# Voltage_Regulator_Board.net
KiCad netlist of a schematic drawn in EAGLE
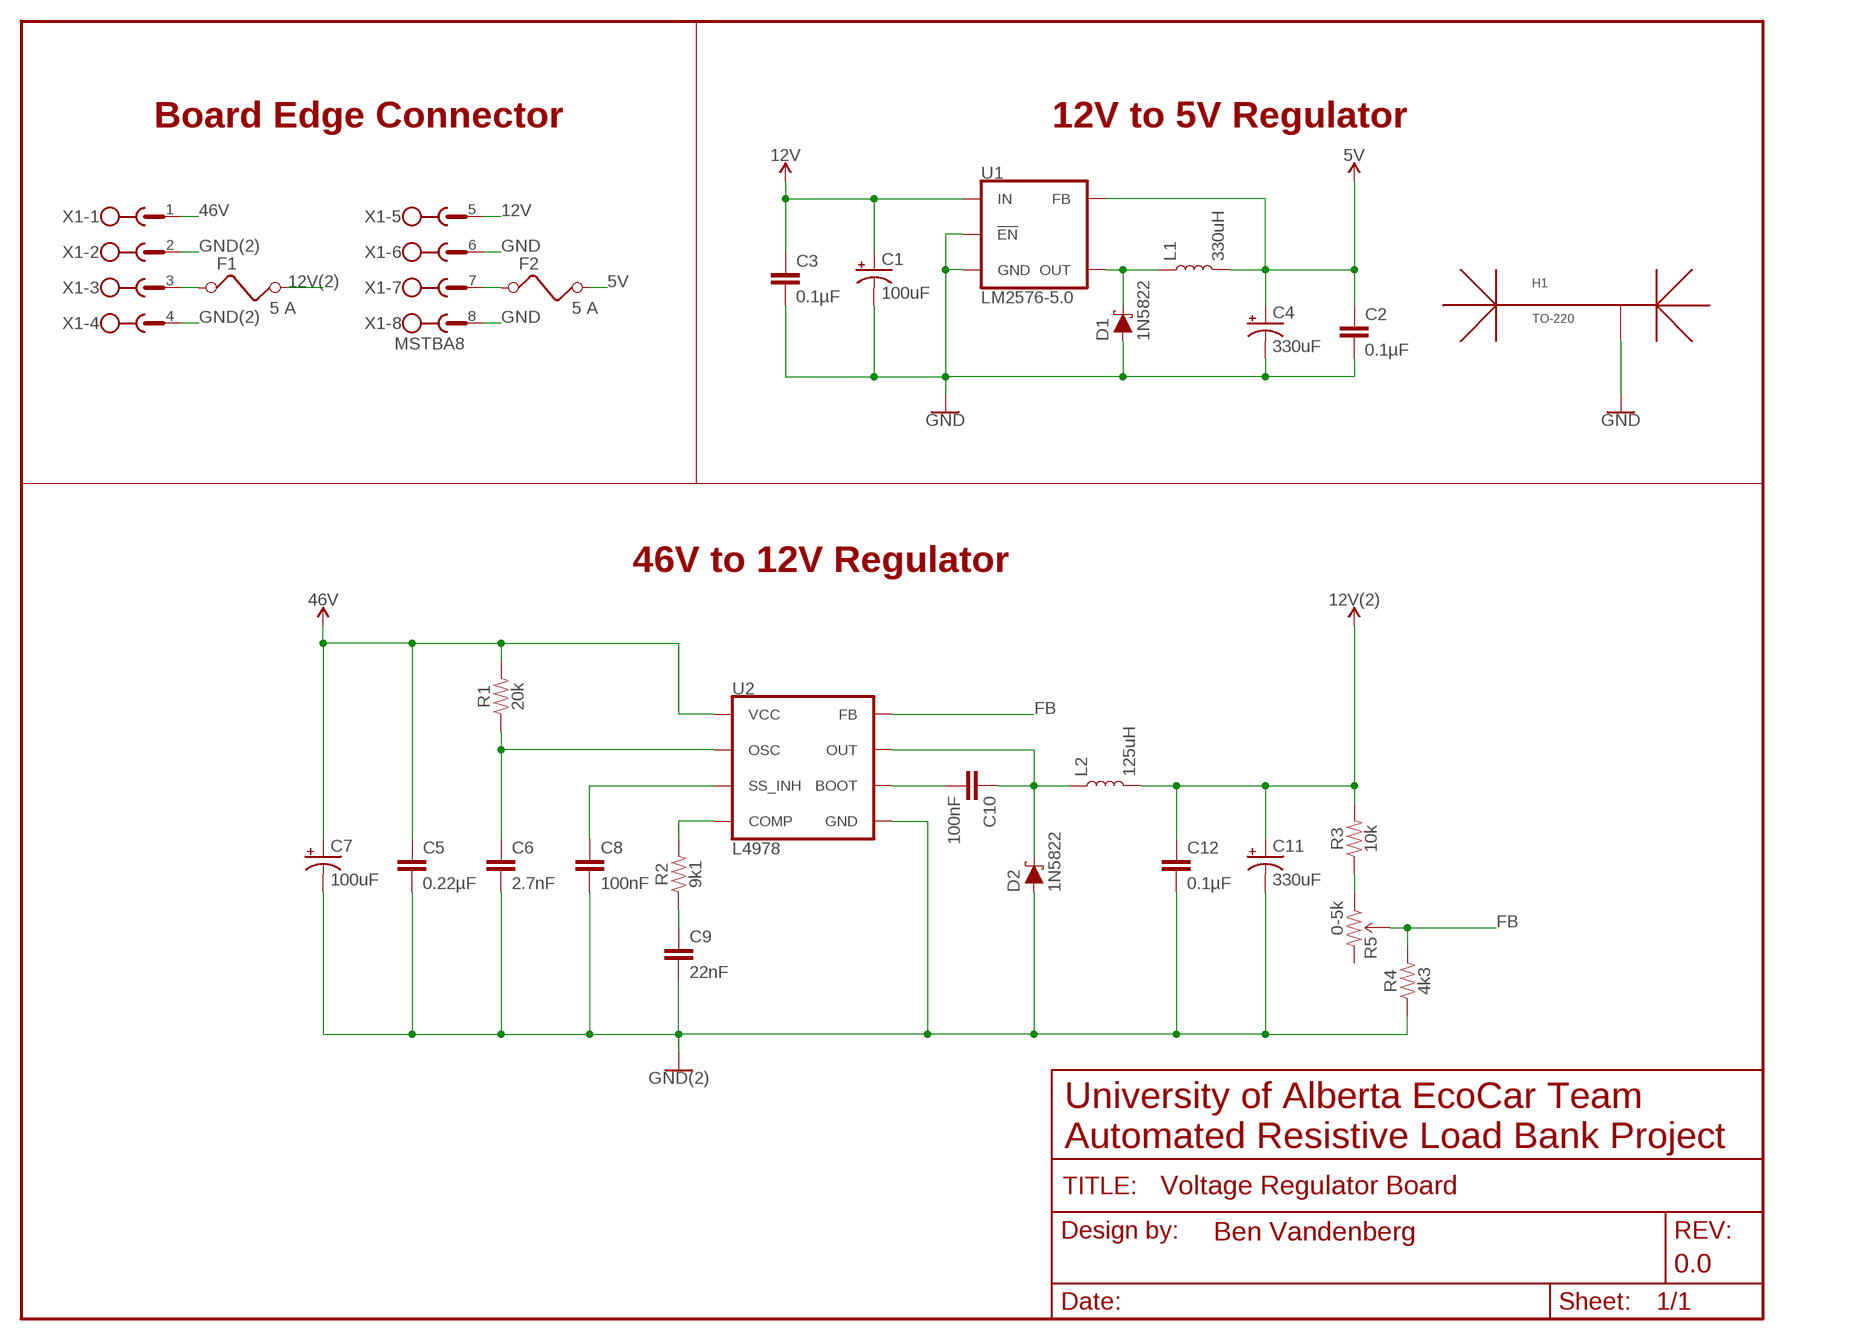
[diagram p0: schematic, sheet 1]

(export (version "E")
  (design (tool "Eeschema 10.0.6"))
  (components
    (comp (ref "C1")
      (value "100uF")
      (footprint "eagle-import:CPOL-RADIAL-3.5MM-8MM")
      (libsource (lib "eagle-import") (part "100UF_POLAR_CAP_WURTH"))
    )
    (comp (ref "C2")
      (value "0.1µF")
      (footprint "eagle-import:0805")
      (libsource (lib "eagle-import") (part "0.33UF/330NF-0805-50V-10%"))
    )
    (comp (ref "C3")
      (value "0.1µF")
      (footprint "eagle-import:0805")
      (libsource (lib "eagle-import") (part "0.33UF/330NF-0805-50V-10%"))
    )
    (comp (ref "C4")
      (value "330uF")
      (footprint "eagle-import:CPOL-RADIAL-5MM-10MM")
      (libsource (lib "eagle-import") (part "330UF_POLAR_CAP_PANASONIC"))
    )
    (comp (ref "C5")
      (value "0.22µF")
      (footprint "eagle-import:0805")
      (libsource (lib "eagle-import") (part "0.33UF/330NF-0805-50V-10%"))
    )
    (comp (ref "C6")
      (value "2.7nF")
      (footprint "eagle-import:0805")
      (libsource (lib "eagle-import") (part "0.33UF/330NF-0805-50V-10%"))
    )
    (comp (ref "C7")
      (value "100uF")
      (footprint "eagle-import:CPOL-RADIAL-3.5MM-8MM")
      (libsource (lib "eagle-import") (part "100UF_POLAR_CAP_WURTH"))
    )
    (comp (ref "C8")
      (value "100nF")
      (footprint "eagle-import:0805")
      (libsource (lib "eagle-import") (part "0.33UF/330NF-0805-50V-10%"))
    )
    (comp (ref "C9")
      (value "22nF")
      (footprint "eagle-import:0805")
      (libsource (lib "eagle-import") (part "0.33UF/330NF-0805-50V-10%"))
    )
    (comp (ref "C10")
      (value "100nF")
      (footprint "eagle-import:0805")
      (libsource (lib "eagle-import") (part "0.33UF/330NF-0805-50V-10%"))
    )
    (comp (ref "C11")
      (value "330uF")
      (footprint "eagle-import:CPOL-RADIAL-5MM-10MM")
      (libsource (lib "eagle-import") (part "330UF_POLAR_CAP_PANASONIC"))
    )
    (comp (ref "C12")
      (value "0.1µF")
      (footprint "eagle-import:0805")
      (libsource (lib "eagle-import") (part "0.33UF/330NF-0805-50V-10%"))
    )
    (comp (ref "D1")
      (value "1N5822")
      (footprint "eagle-import:DO201T15")
      (libsource (lib "eagle-import") (part "1N5822_SCHOTTKY_DIODE"))
    )
    (comp (ref "D2")
      (value "1N5822")
      (footprint "eagle-import:DO201T15")
      (libsource (lib "eagle-import") (part "1N5822_SCHOTTKY_DIODE"))
    )
    (comp (ref "F1")
      (value "5 A")
      (footprint "eagle-import:KEYSTONE_ATM_FUSEHOLDER")
      (libsource (lib "eagle-import") (part "KEYSTONE_ATM_FUSEHOLDER"))
    )
    (comp (ref "F2")
      (value "5 A")
      (footprint "eagle-import:KEYSTONE_ATM_FUSEHOLDER")
      (libsource (lib "eagle-import") (part "KEYSTONE_ATM_FUSEHOLDER"))
    )
    (comp (ref "FRAME1")
      (value "FRAME-LETTERNO_PACKAGE")
      (footprint "eagle-import:DUMMY")
      (fields
        (field (name "DESIGNER") "Nobody")
        (field (name "DESIGNER_1") "Ben Vandenberg")
        (field (name "REV") "0.0")
      )
      (libsource (lib "eagle-import") (part "FRAME-LETTERNO_PACKAGE"))
    )
    (comp (ref "H1")
      (value "TO-220")
      (footprint "eagle-import:HSE-B250-04H_HEATSINK")
      (libsource (lib "eagle-import") (part "HSE-B630-04H_HEATSINK"))
    )
    (comp (ref "L1")
      (value "330uH")
      (footprint "eagle-import:330UH_PTH_INDUCTOR")
      (libsource (lib "eagle-import") (part "HCTI-330-5.2_TOROIDAL_INDUCTOR"))
    )
    (comp (ref "L2")
      (value "125uH")
      (footprint "eagle-import:125UH_PTH_INDUCTOR")
      (libsource (lib "eagle-import") (part "1536W_RF_CHOKE"))
    )
    (comp (ref "R1")
      (value "20k")
      (footprint "eagle-import:0805")
      (libsource (lib "eagle-import") (part "0.75OHM-0805-1/4W-1%"))
    )
    (comp (ref "R2")
      (value "9k1")
      (footprint "eagle-import:0805")
      (libsource (lib "eagle-import") (part "0.75OHM-0805-1/4W-1%"))
    )
    (comp (ref "R3")
      (value "10k")
      (footprint "eagle-import:0805")
      (libsource (lib "eagle-import") (part "0.75OHM-0805-1/4W-1%"))
    )
    (comp (ref "R4")
      (value "4k3")
      (footprint "eagle-import:0805")
      (libsource (lib "eagle-import") (part "0.75OHM-0805-1/4W-1%"))
    )
    (comp (ref "R5")
      (value "0-5k")
      (footprint "eagle-import:TRIM_POT")
      (libsource (lib "eagle-import") (part "CT6EP502_TRIM_POT"))
    )
    (comp (ref "U1")
      (value "LM2576-5.0")
      (footprint "eagle-import:TO220-5")
      (libsource (lib "eagle-import") (part "LM2576_5-0_VOLTAGE_REG"))
    )
    (comp (ref "U2")
      (value "L4978")
      (footprint "eagle-import:DIP08")
      (libsource (lib "eagle-import") (part "L4978_VOLTAGE_REG"))
    )
    (comp (ref "X1")
      (value "MSTBA8")
      (footprint "eagle-import:MSTBA8")
      (fields (field (name "MF") "FARNELL") (field (name "MPN") "1757307"))
      (libsource (lib "eagle-import") (part "MSTBA8"))
    )
  )
  (nets
    (net (code "1") (name "/FB") (class "Default")
      (node (ref "R4") (pin "2") (pinfunction "2_2") (pintype "passive"))
      (node (ref "R5") (pin "2") (pinfunction "WIPER_2") (pintype "passive"))
      (node (ref "U2") (pin "8") (pinfunction "FB_8") (pintype "passive"))
    )
    (net (code "2") (name "5V") (class "Default")
      (node (ref "C2") (pin "1") (pinfunction "1_1") (pintype "passive"))
      (node (ref "C4") (pin "+") (pinfunction "+_+") (pintype "passive"))
      (node (ref "F2") (pin "R1") (pinfunction "2_R1") (pintype "passive"))
      (node (ref "F2") (pin "R2") (pinfunction "2_R2") (pintype "passive"))
      (node (ref "L1") (pin "P$2") (pinfunction "2_P$2") (pintype "passive"))
      (node (ref "U1") (pin "4") (pinfunction "FB_4") (pintype "passive"))
    )
    (net (code "3") (name "12V") (class "Default")
      (node (ref "C1") (pin "+") (pinfunction "+_+") (pintype "passive"))
      (node (ref "C3") (pin "1") (pinfunction "1_1") (pintype "passive"))
      (node (ref "U1") (pin "1") (pinfunction "IN_1") (pintype "input"))
      (node (ref "X1") (pin "5") (pinfunction "1_5") (pintype "passive"))
    )
    (net (code "4") (name "12V(2)") (class "Default")
      (node (ref "C11") (pin "+") (pinfunction "+_+") (pintype "passive"))
      (node (ref "C12") (pin "1") (pinfunction "1_1") (pintype "passive"))
      (node (ref "F1") (pin "R1") (pinfunction "2_R1") (pintype "passive"))
      (node (ref "F1") (pin "R2") (pinfunction "2_R2") (pintype "passive"))
      (node (ref "L2") (pin "P$2") (pinfunction "2_P$2") (pintype "passive"))
      (node (ref "R3") (pin "2") (pinfunction "2_2") (pintype "passive"))
    )
    (net (code "5") (name "46V") (class "Default")
      (node (ref "C5") (pin "1") (pinfunction "1_1") (pintype "passive"))
      (node (ref "C7") (pin "+") (pinfunction "+_+") (pintype "passive"))
      (node (ref "R1") (pin "2") (pinfunction "2_2") (pintype "passive"))
      (node (ref "U2") (pin "5") (pinfunction "VCC_5") (pintype "input"))
      (node (ref "X1") (pin "1") (pinfunction "1_1") (pintype "passive"))
    )
    (net (code "6") (name "GND") (class "Default")
      (node (ref "C1") (pin "-") (pinfunction "-_-") (pintype "passive"))
      (node (ref "C2") (pin "2") (pinfunction "2_2") (pintype "passive"))
      (node (ref "C3") (pin "2") (pinfunction "2_2") (pintype "passive"))
      (node (ref "C4") (pin "-") (pinfunction "-_-") (pintype "passive"))
      (node (ref "D1") (pin "A") (pinfunction "A_A") (pintype "passive"))
      (node (ref "H1") (pin "GND@1") (pinfunction "GND_GND@1") (pintype "bidirectional"))
      (node (ref "H1") (pin "GND@2") (pinfunction "GND_GND@2") (pintype "bidirectional"))
      (node (ref "U1") (pin "3") (pinfunction "GND_3") (pintype "input"))
      (node (ref "U1") (pin "5") (pinfunction "~{EN}_5") (pintype "input"))
      (node (ref "X1") (pin "6") (pinfunction "1_6") (pintype "passive"))
      (node (ref "X1") (pin "8") (pinfunction "1_8") (pintype "passive"))
    )
    (net (code "7") (name "GND(2)") (class "Default")
      (node (ref "C11") (pin "-") (pinfunction "-_-") (pintype "passive"))
      (node (ref "C12") (pin "2") (pinfunction "2_2") (pintype "passive"))
      (node (ref "C5") (pin "2") (pinfunction "2_2") (pintype "passive"))
      (node (ref "C6") (pin "2") (pinfunction "2_2") (pintype "passive"))
      (node (ref "C7") (pin "-") (pinfunction "-_-") (pintype "passive"))
      (node (ref "C8") (pin "2") (pinfunction "2_2") (pintype "passive"))
      (node (ref "C9") (pin "2") (pinfunction "2_2") (pintype "passive"))
      (node (ref "D2") (pin "A") (pinfunction "A_A") (pintype "passive"))
      (node (ref "R4") (pin "1") (pinfunction "1_1") (pintype "passive"))
      (node (ref "U2") (pin "1") (pinfunction "GND_1") (pintype "input"))
      (node (ref "X1") (pin "2") (pinfunction "1_2") (pintype "passive"))
      (node (ref "X1") (pin "4") (pinfunction "1_4") (pintype "passive"))
    )
    (net (code "8") (name "Net-(C9-Pad1)") (class "Default")
      (node (ref "C9") (pin "1") (pinfunction "1_1") (pintype "passive"))
      (node (ref "R2") (pin "1") (pinfunction "1_1") (pintype "passive"))
    )
    (net (code "9") (name "Net-(L1-1)") (class "Default")
      (node (ref "D1") (pin "C") (pinfunction "C_C") (pintype "passive"))
      (node (ref "L1") (pin "P$1") (pinfunction "1_P$1") (pintype "passive"))
      (node (ref "U1") (pin "2") (pinfunction "OUT_2") (pintype "input"))
    )
    (net (code "10") (name "Net-(L2-1)") (class "Default")
      (node (ref "C10") (pin "1") (pinfunction "1_1") (pintype "passive"))
      (node (ref "D2") (pin "C") (pinfunction "C_C") (pintype "passive"))
      (node (ref "L2") (pin "P$1") (pinfunction "1_P$1") (pintype "passive"))
      (node (ref "U2") (pin "4") (pinfunction "OUT_4") (pintype "passive"))
    )
    (net (code "11") (name "Net-(R5-CCW)") (class "Default")
      (node (ref "R3") (pin "1") (pinfunction "1_1") (pintype "passive"))
      (node (ref "R5") (pin "1") (pinfunction "CCW_1") (pintype "passive"))
    )
    (net (code "12") (name "Net-(U2-BOOT)") (class "Default")
      (node (ref "C10") (pin "2") (pinfunction "2_2") (pintype "passive"))
      (node (ref "U2") (pin "6") (pinfunction "BOOT_6") (pintype "input"))
    )
    (net (code "13") (name "Net-(U2-COMP)") (class "Default")
      (node (ref "R2") (pin "2") (pinfunction "2_2") (pintype "passive"))
      (node (ref "U2") (pin "7") (pinfunction "COMP_7") (pintype "input"))
    )
    (net (code "14") (name "Net-(U2-OSC)") (class "Default")
      (node (ref "C6") (pin "1") (pinfunction "1_1") (pintype "passive"))
      (node (ref "R1") (pin "1") (pinfunction "1_1") (pintype "passive"))
      (node (ref "U2") (pin "3") (pinfunction "OSC_3") (pintype "input"))
    )
    (net (code "15") (name "Net-(U2-SS_INH)") (class "Default")
      (node (ref "C8") (pin "1") (pinfunction "1_1") (pintype "passive"))
      (node (ref "U2") (pin "2") (pinfunction "SS_INH_2") (pintype "input"))
    )
    (net (code "16") (name "Net-(X1C-1)") (class "Default")
      (node (ref "F1") (pin "L1") (pinfunction "1_L1") (pintype "passive"))
      (node (ref "F1") (pin "L2") (pinfunction "1_L2") (pintype "passive"))
      (node (ref "X1") (pin "3") (pinfunction "1_3") (pintype "passive"))
    )
    (net (code "17") (name "Net-(X1G-1)") (class "Default")
      (node (ref "F2") (pin "L1") (pinfunction "1_L1") (pintype "passive"))
      (node (ref "F2") (pin "L2") (pinfunction "1_L2") (pintype "passive"))
      (node (ref "X1") (pin "7") (pinfunction "1_7") (pintype "passive"))
    )
    (net (code "18") (name "unconnected-(R5-CW-Pad3)") (class "Default")
      (node (ref "R5") (pin "3") (pinfunction "CW_3") (pintype "passive"))
    )
  )
)
